# CH32V467RET-R0.net
KiCad netlist of a schematic drawn in Altium Designer
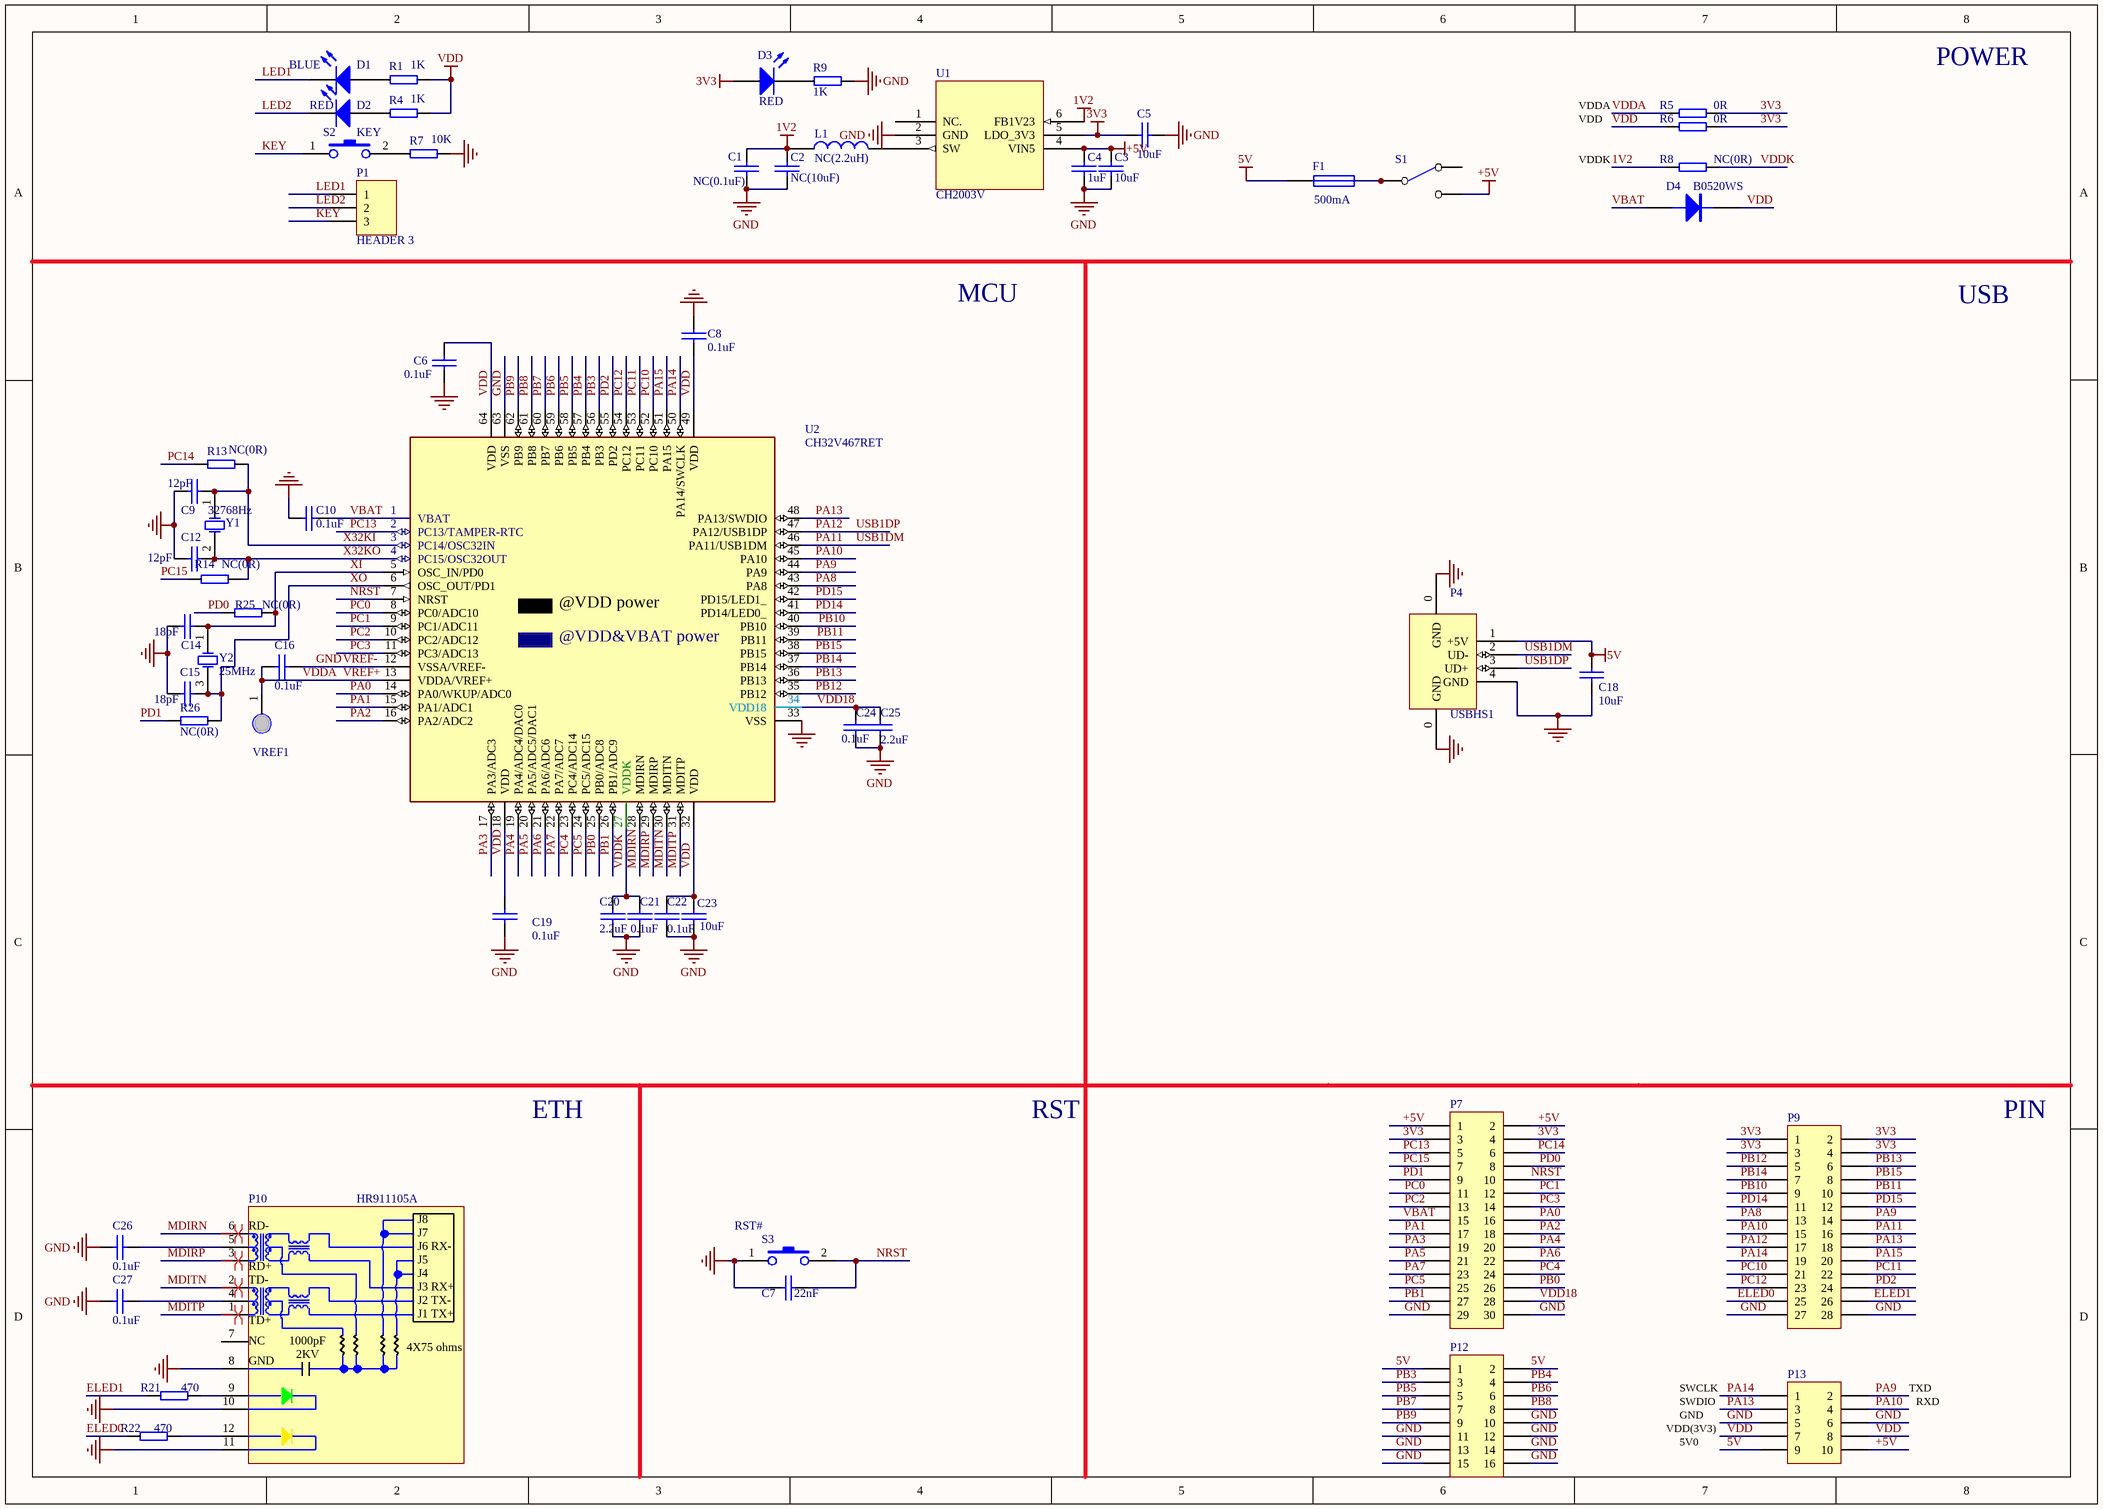
[diagram p0: CH32V467RET-R0.SchDoc]

(export (version "E")
  (design (tool "Eeschema 10.0.6"))
  (components
    (comp (ref "C1")
      (value "NC(0.1uF)")
      (footprint "0402_C")
      (description "Capacitor")
      (libsource (lib "") (part "CAP_2"))
    )
    (comp (ref "C2")
      (value "NC(10uF)")
      (footprint "0603_C")
      (description "Capacitor")
      (libsource (lib "") (part "CAP_1"))
    )
    (comp (ref "C3")
      (value "10uF")
      (footprint "0603_C")
      (description "Capacitor")
      (libsource (lib "") (part "CAP_1"))
    )
    (comp (ref "C4")
      (value "1uF")
      (footprint "0402_C")
      (description "Capacitor")
      (libsource (lib "") (part "CAP_2"))
    )
    (comp (ref "C5")
      (value "10uF")
      (footprint "0603_C")
      (description "Capacitor")
      (libsource (lib "") (part "CAP_1"))
    )
    (comp (ref "C6")
      (value "0.1uF")
      (footprint "0402_C")
      (description "Capacitor")
      (libsource (lib "") (part "CAP_1"))
    )
    (comp (ref "C7")
      (value "22nF")
      (footprint "0402_C")
      (description "Capacitor")
      (libsource (lib "*") (part "CAP"))
    )
    (comp (ref "C8")
      (value "0.1uF")
      (footprint "0402_C")
      (description "Capacitor")
      (libsource (lib "") (part "CAP_1"))
    )
    (comp (ref "C9")
      (value "12pF")
      (footprint "0402_C")
      (description "Capacitor")
      (libsource (lib "") (part "CAP_1"))
    )
    (comp (ref "C10")
      (value "0.1uF")
      (footprint "0402_C")
      (description "Capacitor")
      (libsource (lib "") (part "CAP_1"))
    )
    (comp (ref "C12")
      (value "12pF")
      (footprint "0402_C")
      (description "Capacitor")
      (libsource (lib "") (part "CAP_1"))
    )
    (comp (ref "C14")
      (value "18pF")
      (footprint "0402_C")
      (description "Capacitor")
      (libsource (lib "") (part "CAP_1"))
    )
    (comp (ref "C15")
      (value "18pF")
      (footprint "0402_C")
      (description "Capacitor")
      (libsource (lib "") (part "CAP_1"))
    )
    (comp (ref "C16")
      (value "0.1uF")
      (footprint "0402_C")
      (description "Capacitor")
      (libsource (lib "") (part "CAP_1"))
    )
    (comp (ref "C18")
      (value "10uF")
      (footprint "0603_C")
      (description "Capacitor")
      (libsource (lib "*") (part "CAP"))
    )
    (comp (ref "C19")
      (value "0.1uF")
      (footprint "0402_C")
      (description "Capacitor")
      (libsource (lib "") (part "CAP_1"))
    )
    (comp (ref "C20")
      (value "2.2uF")
      (footprint "0402_C")
      (description "Capacitor")
      (libsource (lib "") (part "CAP_1"))
    )
    (comp (ref "C21")
      (value "0.1uF")
      (footprint "0402_C")
      (description "Capacitor")
      (libsource (lib "") (part "CAP_1"))
    )
    (comp (ref "C22")
      (value "0.1uF")
      (footprint "0402_C")
      (description "Capacitor")
      (libsource (lib "") (part "CAP_1"))
    )
    (comp (ref "C23")
      (value "10uF")
      (footprint "0603_C")
      (description "Capacitor")
      (libsource (lib "wch_sch_others") (part "CAP"))
    )
    (comp (ref "C24")
      (value "0.1uF")
      (footprint "0402_C")
      (description "Capacitor")
      (libsource (lib "") (part "CAP_1"))
    )
    (comp (ref "C25")
      (value "2.2uF")
      (footprint "0402_C")
      (description "Capacitor")
      (libsource (lib "") (part "CAP_1"))
    )
    (comp (ref "C26")
      (value "0.1uF")
      (footprint "0402_C")
      (description "Capacitor")
      (libsource (lib "wch_sch_others") (part "CAP"))
    )
    (comp (ref "C27")
      (value "0.1uF")
      (footprint "0402_C")
      (description "Capacitor")
      (libsource (lib "wch_sch_others") (part "CAP"))
    )
    (comp (ref "D1")
      (value "BLUE")
      (footprint "0603+")
      (description "Typical INFRARED GaAs LED")
      (fields (field (name "PUBLISHER") "Altium Limited"))
      (libsource (lib "*") (part "LED0"))
    )
    (comp (ref "D2")
      (value "RED")
      (footprint "0603+")
      (description "Typical INFRARED GaAs LED")
      (fields (field (name "PUBLISHER") "Altium Limited"))
      (libsource (lib "*") (part "LED0"))
    )
    (comp (ref "D3")
      (value "RED")
      (footprint "0603+")
      (description "Typical INFRARED GaAs LED")
      (fields (field (name "PUBLISHER") "Altium Limited"))
      (libsource (lib "*") (part "LED0"))
    )
    (comp (ref "D4")
      (value "B0520WS")
      (footprint "SOD-323")
      (description "Diode")
      (libsource (lib "*") (part "DIODE"))
    )
    (comp (ref "F1")
      (value "500mA")
      (footprint "0603")
      (description "Fuse")
      (libsource (lib "wch_sch_others") (part "FUSE1"))
    )
    (comp (ref "L1") (value "NC(2.2uH)") (footprint "CD32") (libsource (lib "*") (part "INDUCTOR")))
    (comp (ref "P1")
      (value "HEADER 3")
      (footprint "SIP3-2.54MM")
      (description "Header, 3-Pin")
      (libsource (lib "wch_sch_others") (part "HEADER 3"))
    )
    (comp (ref "P4")
      (value "USBHS1")
      (footprint "USBAF")
      (description "USB Port")
      (libsource (lib "*") (part "USB"))
    )
    (comp (ref "P7")
      (value "HEADER 15x2")
      (footprint "MYPCB:IDC30-2.54MM")
      (description "Header, 15-Pin, Dual row")
      (libsource (lib "wch_sch_others") (part "HEADER 15x2"))
    )
    (comp (ref "P9")
      (value "HEADER 14x2")
      (footprint "MYPCB:IDC28-2.54MM")
      (description "Header, 14-Pin, Dual row")
      (libsource (lib "wch_sch_others") (part "HEADER 14x2"))
    )
    (comp (ref "P10") (value "HR911105A") (footprint "HR911105A") (libsource (lib "*") (part "HR911105A")))
    (comp (ref "P12")
      (value "Ppin")
      (footprint "IDC16-2.54mm")
      (description "Header, 8-Pin, Dual row, Right Angle")
      (fields (field (name "PUBLISHER") "Altium Limited"))
      (libsource (lib "Miscellaneous Connectors") (part "Header 8X2H"))
    )
    (comp (ref "P13")
      (value "LINK")
      (footprint "IDC10-2.54mm")
      (description "Header, 5-Pin, Dual row, Right Angle")
      (fields (field (name "PUBLISHER") "Altium Limited"))
      (libsource (lib "Miscellaneous Connectors") (part "Header 5X2H"))
    )
    (comp (ref "R1") (value "1K") (footprint "0402") (libsource (lib "wch_sch_others") (part "RES")))
    (comp (ref "R4") (value "1K") (footprint "0402") (libsource (lib "wch_sch_others") (part "RES")))
    (comp (ref "R5") (value "0R") (footprint "0402") (libsource (lib "*") (part "R")))
    (comp (ref "R6") (value "0R") (footprint "0402") (libsource (lib "*") (part "R")))
    (comp (ref "R7") (value "10K") (footprint "0402") (libsource (lib "wch_sch_others") (part "RES")))
    (comp (ref "R8") (value "NC(0R)") (footprint "0402") (libsource (lib "*") (part "R")))
    (comp (ref "R9") (value "1K") (footprint "0402") (libsource (lib "wch_sch_others") (part "RES")))
    (comp (ref "R13") (value "NC(0R)") (footprint "0402") (libsource (lib "wch_sch_others") (part "RES")))
    (comp (ref "R14") (value "NC(0R)") (footprint "0402") (libsource (lib "wch_sch_others") (part "RES")))
    (comp (ref "R21") (value "470") (footprint "0402") (libsource (lib "wch_sch_others") (part "RES")))
    (comp (ref "R22") (value "470") (footprint "0402") (libsource (lib "wch_sch_others") (part "RES")))
    (comp (ref "R25") (value "NC(0R)") (footprint "0402") (libsource (lib "wch_sch_others") (part "RES")))
    (comp (ref "R26") (value "NC(0R)") (footprint "0402") (libsource (lib "wch_sch_others") (part "RES")))
    (comp (ref "S1") (value "SW SPDT") (footprint "SW1") (libsource (lib "*") (part "SW SPDT")))
    (comp (ref "S2")
      (value "KEY")
      (footprint "SMD_6.1x3.65x2.5mm-KEY")
      (libsource (lib "wch_sch_others") (part "KEY1"))
    )
    (comp (ref "S3")
      (value "RST#")
      (footprint "SMD_6.1x3.65x2.5mm-KEY")
      (libsource (lib "wch_sch_others") (part "KEY1"))
    )
    (comp (ref "U1")
      (value "CH2003V")
      (footprint "SOT-23-6")
      (description "Step-Down DC-DC Converter, 5V input, 1.23V * 800mA output, with LDO 3.3V * 200mA")
      (libsource (lib "CHXXX") (part "CH2003V"))
    )
    (comp (ref "U2")
      (value "CH32V467RET")
      (footprint "LQFP64_7X7")
      (description "RISC-V FPU HD-MCU, 175MHz, USB_480M, 100M Ethernet & Phy, CAN, ADC, DAC, SRAM")
      (libsource (lib "CHXXX") (part "CH32V467RET"))
    )
    (comp (ref "VREF1")
      (value "PAD")
      (footprint "TESTPOINT1")
      (description "焊盘")
      (libsource (lib "wch_sch_others") (part "PAD"))
    )
    (comp (ref "Y1")
      (value "32768Hz")
      (footprint "FC-135")
      (description "Crystal Oscillator")
      (fields (field (name "PUBLISHER") "Altium Limited"))
      (libsource (lib "*") (part "XTAL"))
    )
    (comp (ref "Y2")
      (value "25MHz")
      (footprint "XT3225")
      (description "Crystal Oscillator")
      (fields (field (name "PUBLISHER") "Altium Limited"))
      (libsource (lib "") (part "XTAL_1"))
    )
  )
  (nets
    (net (code "1") (name "+5V") (class "Default")
      (node (ref "C3") (pin "2") (pinfunction "2_2") (pintype "passive"))
      (node (ref "C4") (pin "2") (pinfunction "2_2") (pintype "passive"))
      (node (ref "P13") (pin "10") (pinfunction "10_10") (pintype "passive"))
      (node (ref "P7") (pin "1") (pinfunction "1_1") (pintype "passive"))
      (node (ref "P7") (pin "2") (pinfunction "2_2") (pintype "passive"))
      (node (ref "S1") (pin "2") (pinfunction "NC_2") (pintype "passive"))
      (node (ref "U1") (pin "4") (pinfunction "VIN5_4") (pintype "power_in"))
    )
    (net (code "3") (name "/ELED0") (class "Default")
      (node (ref "P9") (pin "25") (pinfunction "25_25") (pintype "passive"))
      (node (ref "R22") (pin "1") (pintype "passive"))
    )
    (net (code "4") (name "/ELED1") (class "Default")
      (node (ref "P9") (pin "26") (pinfunction "26_26") (pintype "passive"))
      (node (ref "R21") (pin "1") (pintype "passive"))
    )
    (net (code "5") (name "/KEY") (class "Default")
      (node (ref "P1") (pin "3") (pinfunction "3_3") (pintype "passive"))
      (node (ref "S2") (pin "1") (pinfunction "1_1") (pintype "passive"))
    )
    (net (code "6") (name "/LED1") (class "Default")
      (node (ref "D1") (pin "2") (pinfunction "K_2") (pintype "passive"))
      (node (ref "P1") (pin "1") (pinfunction "1_1") (pintype "passive"))
    )
    (net (code "7") (name "/LED2") (class "Default")
      (node (ref "D2") (pin "2") (pinfunction "K_2") (pintype "passive"))
      (node (ref "P1") (pin "2") (pinfunction "2_2") (pintype "passive"))
    )
    (net (code "8") (name "/MDIRN") (class "Default")
      (node (ref "P10") (pin "6") (pintype "passive"))
      (node (ref "U2") (pin "28") (pinfunction "MDIRN_28") (pintype "bidirectional"))
    )
    (net (code "9") (name "/MDIRP") (class "Default")
      (node (ref "P10") (pin "3") (pintype "passive"))
      (node (ref "U2") (pin "29") (pinfunction "MDIRP_29") (pintype "bidirectional"))
    )
    (net (code "10") (name "/MDITN") (class "Default")
      (node (ref "P10") (pin "2") (pintype "passive"))
      (node (ref "U2") (pin "30") (pinfunction "MDITN_30") (pintype "bidirectional"))
    )
    (net (code "11") (name "/MDITP") (class "Default")
      (node (ref "P10") (pin "1") (pintype "passive"))
      (node (ref "U2") (pin "31") (pinfunction "MDITP_31") (pintype "bidirectional"))
    )
    (net (code "12") (name "/NRST") (class "Default")
      (node (ref "C7") (pin "2") (pinfunction "2_2") (pintype "passive"))
      (node (ref "P7") (pin "10") (pinfunction "10_10") (pintype "passive"))
      (node (ref "S3") (pin "2") (pinfunction "2_2") (pintype "passive"))
      (node (ref "U2") (pin "7") (pinfunction "NRST_7") (pintype "input"))
    )
    (net (code "13") (name "/PA0") (class "Default")
      (node (ref "P7") (pin "16") (pinfunction "16_16") (pintype "passive"))
      (node (ref "U2") (pin "14") (pinfunction "PA0/WKUP/ADC0_14") (pintype "bidirectional"))
    )
    (net (code "14") (name "/PA1") (class "Default")
      (node (ref "P7") (pin "17") (pinfunction "17_17") (pintype "passive"))
      (node (ref "U2") (pin "15") (pinfunction "PA1/ADC1_15") (pintype "bidirectional"))
    )
    (net (code "15") (name "/PA2") (class "Default")
      (node (ref "P7") (pin "18") (pinfunction "18_18") (pintype "passive"))
      (node (ref "U2") (pin "16") (pinfunction "PA2/ADC2_16") (pintype "bidirectional"))
    )
    (net (code "16") (name "/PA3") (class "Default")
      (node (ref "P7") (pin "19") (pinfunction "19_19") (pintype "passive"))
      (node (ref "U2") (pin "17") (pinfunction "PA3/ADC3_17") (pintype "bidirectional"))
    )
    (net (code "17") (name "/PA4") (class "Default")
      (node (ref "P7") (pin "20") (pinfunction "20_20") (pintype "passive"))
      (node (ref "U2") (pin "19") (pinfunction "PA4/ADC4/DAC0_19") (pintype "bidirectional"))
    )
    (net (code "18") (name "/PA5") (class "Default")
      (node (ref "P7") (pin "21") (pinfunction "21_21") (pintype "passive"))
      (node (ref "U2") (pin "20") (pinfunction "PA5/ADC5/DAC1_20") (pintype "bidirectional"))
    )
    (net (code "19") (name "/PA6") (class "Default")
      (node (ref "P7") (pin "22") (pinfunction "22_22") (pintype "passive"))
      (node (ref "U2") (pin "21") (pinfunction "PA6/ADC6_21") (pintype "bidirectional"))
    )
    (net (code "20") (name "/PA7") (class "Default")
      (node (ref "P7") (pin "23") (pinfunction "23_23") (pintype "passive"))
      (node (ref "U2") (pin "22") (pinfunction "PA7/ADC7_22") (pintype "bidirectional"))
    )
    (net (code "21") (name "/PA8") (class "Default")
      (node (ref "P9") (pin "13") (pinfunction "13_13") (pintype "passive"))
      (node (ref "U2") (pin "43") (pinfunction "PA8_43") (pintype "bidirectional"))
    )
    (net (code "22") (name "/PA9") (class "Default")
      (node (ref "P13") (pin "2") (pinfunction "2_2") (pintype "passive"))
      (node (ref "P9") (pin "14") (pinfunction "14_14") (pintype "passive"))
      (node (ref "U2") (pin "44") (pinfunction "PA9_44") (pintype "bidirectional"))
    )
    (net (code "23") (name "/PA10") (class "Default")
      (node (ref "P13") (pin "4") (pinfunction "4_4") (pintype "passive"))
      (node (ref "P9") (pin "15") (pinfunction "15_15") (pintype "passive"))
      (node (ref "U2") (pin "45") (pinfunction "PA10_45") (pintype "bidirectional"))
    )
    (net (code "24") (name "/PA11") (class "Default")
      (node (ref "P4") (pin "2") (pinfunction "UD-_2") (pintype "bidirectional"))
      (node (ref "P9") (pin "16") (pinfunction "16_16") (pintype "passive"))
      (node (ref "U2") (pin "46") (pinfunction "PA11/USB1DM_46") (pintype "bidirectional"))
    )
    (net (code "25") (name "/PA12") (class "Default")
      (node (ref "P4") (pin "3") (pinfunction "UD+_3") (pintype "bidirectional"))
      (node (ref "P9") (pin "17") (pinfunction "17_17") (pintype "passive"))
      (node (ref "U2") (pin "47") (pinfunction "PA12/USB1DP_47") (pintype "bidirectional"))
    )
    (net (code "26") (name "/PA13") (class "Default")
      (node (ref "P13") (pin "3") (pinfunction "3_3") (pintype "passive"))
      (node (ref "P9") (pin "18") (pinfunction "18_18") (pintype "passive"))
      (node (ref "U2") (pin "48") (pinfunction "PA13/SWDIO_48") (pintype "bidirectional"))
    )
    (net (code "27") (name "/PA14") (class "Default")
      (node (ref "P13") (pin "1") (pinfunction "1_1") (pintype "passive"))
      (node (ref "P9") (pin "19") (pinfunction "19_19") (pintype "passive"))
      (node (ref "U2") (pin "50") (pinfunction "PA14/SWCLK_50") (pintype "bidirectional"))
    )
    (net (code "28") (name "/PA15") (class "Default")
      (node (ref "P9") (pin "20") (pinfunction "20_20") (pintype "passive"))
      (node (ref "U2") (pin "51") (pinfunction "PA15_51") (pintype "bidirectional"))
    )
    (net (code "29") (name "/PB0") (class "Default")
      (node (ref "P7") (pin "26") (pinfunction "26_26") (pintype "passive"))
      (node (ref "U2") (pin "25") (pinfunction "PB0/ADC8_25") (pintype "bidirectional"))
    )
    (net (code "30") (name "/PB1") (class "Default")
      (node (ref "P7") (pin "27") (pinfunction "27_27") (pintype "passive"))
      (node (ref "U2") (pin "26") (pinfunction "PB1/ADC9_26") (pintype "bidirectional"))
    )
    (net (code "31") (name "/PB3") (class "Default")
      (node (ref "P12") (pin "3") (pinfunction "3_3") (pintype "passive"))
      (node (ref "U2") (pin "56") (pinfunction "PB3_56") (pintype "bidirectional"))
    )
    (net (code "32") (name "/PB4") (class "Default")
      (node (ref "P12") (pin "4") (pinfunction "4_4") (pintype "passive"))
      (node (ref "U2") (pin "57") (pinfunction "PB4_57") (pintype "bidirectional"))
    )
    (net (code "33") (name "/PB5") (class "Default")
      (node (ref "P12") (pin "5") (pinfunction "5_5") (pintype "passive"))
      (node (ref "U2") (pin "58") (pinfunction "PB5_58") (pintype "bidirectional"))
    )
    (net (code "34") (name "/PB6") (class "Default")
      (node (ref "P12") (pin "6") (pinfunction "6_6") (pintype "passive"))
      (node (ref "U2") (pin "59") (pinfunction "PB6_59") (pintype "bidirectional"))
    )
    (net (code "35") (name "/PB7") (class "Default")
      (node (ref "P12") (pin "7") (pinfunction "7_7") (pintype "passive"))
      (node (ref "U2") (pin "60") (pinfunction "PB7_60") (pintype "bidirectional"))
    )
    (net (code "36") (name "/PB8") (class "Default")
      (node (ref "P12") (pin "8") (pinfunction "8_8") (pintype "passive"))
      (node (ref "U2") (pin "61") (pinfunction "PB8_61") (pintype "bidirectional"))
    )
    (net (code "37") (name "/PB9") (class "Default")
      (node (ref "P12") (pin "9") (pinfunction "9_9") (pintype "passive"))
      (node (ref "U2") (pin "62") (pinfunction "PB9_62") (pintype "bidirectional"))
    )
    (net (code "38") (name "/PB10") (class "Default")
      (node (ref "P9") (pin "9") (pinfunction "9_9") (pintype "passive"))
      (node (ref "U2") (pin "40") (pinfunction "PB10_40") (pintype "bidirectional"))
    )
    (net (code "39") (name "/PB11") (class "Default")
      (node (ref "P9") (pin "10") (pinfunction "10_10") (pintype "passive"))
      (node (ref "U2") (pin "39") (pinfunction "PB11_39") (pintype "bidirectional"))
    )
    (net (code "40") (name "/PB12") (class "Default")
      (node (ref "P9") (pin "5") (pinfunction "5_5") (pintype "passive"))
      (node (ref "U2") (pin "35") (pinfunction "PB12_35") (pintype "bidirectional"))
    )
    (net (code "41") (name "/PB13") (class "Default")
      (node (ref "P9") (pin "6") (pinfunction "6_6") (pintype "passive"))
      (node (ref "U2") (pin "36") (pinfunction "PB13_36") (pintype "bidirectional"))
    )
    (net (code "42") (name "/PB14") (class "Default")
      (node (ref "P9") (pin "7") (pinfunction "7_7") (pintype "passive"))
      (node (ref "U2") (pin "37") (pinfunction "PB14_37") (pintype "bidirectional"))
    )
    (net (code "43") (name "/PB15") (class "Default")
      (node (ref "P9") (pin "8") (pinfunction "8_8") (pintype "passive"))
      (node (ref "U2") (pin "38") (pinfunction "PB15_38") (pintype "bidirectional"))
    )
    (net (code "44") (name "/PC0") (class "Default")
      (node (ref "P7") (pin "11") (pinfunction "11_11") (pintype "passive"))
      (node (ref "U2") (pin "8") (pinfunction "PC0/ADC10_8") (pintype "bidirectional"))
    )
    (net (code "45") (name "/PC1") (class "Default")
      (node (ref "P7") (pin "12") (pinfunction "12_12") (pintype "passive"))
      (node (ref "U2") (pin "9") (pinfunction "PC1/ADC11_9") (pintype "bidirectional"))
    )
    (net (code "46") (name "/PC2") (class "Default")
      (node (ref "P7") (pin "13") (pinfunction "13_13") (pintype "passive"))
      (node (ref "U2") (pin "10") (pinfunction "PC2/ADC12_10") (pintype "bidirectional"))
    )
    (net (code "47") (name "/PC3") (class "Default")
      (node (ref "P7") (pin "14") (pinfunction "14_14") (pintype "passive"))
      (node (ref "U2") (pin "11") (pinfunction "PC3/ADC13_11") (pintype "bidirectional"))
    )
    (net (code "48") (name "/PC4") (class "Default")
      (node (ref "P7") (pin "24") (pinfunction "24_24") (pintype "passive"))
      (node (ref "U2") (pin "23") (pinfunction "PC4/ADC14_23") (pintype "bidirectional"))
    )
    (net (code "49") (name "/PC5") (class "Default")
      (node (ref "P7") (pin "25") (pinfunction "25_25") (pintype "passive"))
      (node (ref "U2") (pin "24") (pinfunction "PC5/ADC15_24") (pintype "bidirectional"))
    )
    (net (code "50") (name "/PC10") (class "Default")
      (node (ref "P9") (pin "21") (pinfunction "21_21") (pintype "passive"))
      (node (ref "U2") (pin "52") (pinfunction "PC10_52") (pintype "bidirectional"))
    )
    (net (code "51") (name "/PC11") (class "Default")
      (node (ref "P9") (pin "22") (pinfunction "22_22") (pintype "passive"))
      (node (ref "U2") (pin "53") (pinfunction "PC11_53") (pintype "bidirectional"))
    )
    (net (code "52") (name "/PC12") (class "Default")
      (node (ref "P9") (pin "23") (pinfunction "23_23") (pintype "passive"))
      (node (ref "U2") (pin "54") (pinfunction "PC12_54") (pintype "bidirectional"))
    )
    (net (code "53") (name "/PC13") (class "Default")
      (node (ref "P7") (pin "5") (pinfunction "5_5") (pintype "passive"))
      (node (ref "U2") (pin "2") (pinfunction "PC13/TAMPER-RTC_2") (pintype "bidirectional"))
    )
    (net (code "54") (name "/PC14") (class "Default")
      (node (ref "P7") (pin "6") (pinfunction "6_6") (pintype "passive"))
      (node (ref "R13") (pin "1") (pintype "passive"))
    )
    (net (code "55") (name "/PC15") (class "Default")
      (node (ref "P7") (pin "7") (pinfunction "7_7") (pintype "passive"))
      (node (ref "R14") (pin "1") (pintype "passive"))
    )
    (net (code "56") (name "/PD0") (class "Default")
      (node (ref "P7") (pin "8") (pinfunction "8_8") (pintype "passive"))
      (node (ref "R25") (pin "1") (pintype "passive"))
    )
    (net (code "57") (name "/PD1") (class "Default")
      (node (ref "P7") (pin "9") (pinfunction "9_9") (pintype "passive"))
      (node (ref "R26") (pin "2") (pintype "passive"))
    )
    (net (code "58") (name "/PD2") (class "Default")
      (node (ref "P9") (pin "24") (pinfunction "24_24") (pintype "passive"))
      (node (ref "U2") (pin "55") (pinfunction "PD2_55") (pintype "bidirectional"))
    )
    (net (code "59") (name "/PD14") (class "Default")
      (node (ref "P9") (pin "11") (pinfunction "11_11") (pintype "passive"))
      (node (ref "U2") (pin "41") (pinfunction "PD14/LED0__41") (pintype "bidirectional"))
    )
    (net (code "60") (name "/PD15") (class "Default")
      (node (ref "P9") (pin "12") (pinfunction "12_12") (pintype "passive"))
      (node (ref "U2") (pin "42") (pinfunction "PD15/LED1__42") (pintype "bidirectional"))
    )
    (net (code "61") (name "/VBAT") (class "Default")
      (node (ref "C10") (pin "2") (pinfunction "2_2") (pintype "passive"))
      (node (ref "D4") (pin "1") (pinfunction "A_1") (pintype "passive"))
      (node (ref "P7") (pin "15") (pinfunction "15_15") (pintype "passive"))
      (node (ref "U2") (pin "1") (pinfunction "VBAT_1") (pintype "power_in"))
    )
    (net (code "62") (name "/VDD18") (class "Default")
      (node (ref "C24") (pin "2") (pinfunction "2_2") (pintype "passive"))
      (node (ref "C25") (pin "2") (pinfunction "2_2") (pintype "passive"))
      (node (ref "P7") (pin "28") (pinfunction "28_28") (pintype "passive"))
      (node (ref "U2") (pin "34") (pinfunction "VDD18_34") (pintype "power_in"))
    )
    (net (code "63") (name "/VDDA") (class "Default")
      (node (ref "C16") (pin "1") (pinfunction "1_1") (pintype "passive"))
      (node (ref "R5") (pin "2") (pinfunction "2_2") (pintype "passive"))
      (node (ref "U2") (pin "13") (pinfunction "VDDA/VREF+_13") (pintype "power_in"))
      (node (ref "VREF1") (pin "1") (pintype "passive"))
    )
    (net (code "64") (name "/VDDK") (class "Default")
      (node (ref "C20") (pin "2") (pinfunction "2_2") (pintype "passive"))
      (node (ref "C21") (pin "2") (pinfunction "2_2") (pintype "passive"))
      (node (ref "R8") (pin "1") (pinfunction "1_1") (pintype "passive"))
      (node (ref "U2") (pin "27") (pinfunction "VDDK_27") (pintype "power_in"))
    )
    (net (code "65") (name "/X32KI") (class "Default")
      (node (ref "C9") (pin "2") (pinfunction "2_2") (pintype "passive"))
      (node (ref "R13") (pin "2") (pintype "passive"))
      (node (ref "U2") (pin "3") (pinfunction "PC14/OSC32IN_3") (pintype "bidirectional"))
      (node (ref "Y1") (pin "1") (pinfunction "OSC1_1") (pintype "passive"))
    )
    (net (code "66") (name "/X32KO") (class "Default")
      (node (ref "C12") (pin "2") (pinfunction "2_2") (pintype "passive"))
      (node (ref "R14") (pin "2") (pintype "passive"))
      (node (ref "U2") (pin "4") (pinfunction "PC15/OSC32OUT_4") (pintype "bidirectional"))
      (node (ref "Y1") (pin "2") (pinfunction "OSC2_2") (pintype "passive"))
    )
    (net (code "67") (name "/XI") (class "Default")
      (node (ref "C14") (pin "2") (pinfunction "2_2") (pintype "passive"))
      (node (ref "R25") (pin "2") (pintype "passive"))
      (node (ref "U2") (pin "5") (pinfunction "OSC_IN/PD0_5") (pintype "input"))
      (node (ref "Y2") (pin "1") (pinfunction "OSC1_1") (pintype "passive"))
    )
    (net (code "68") (name "/XO") (class "Default")
      (node (ref "C15") (pin "2") (pinfunction "2_2") (pintype "passive"))
      (node (ref "R26") (pin "1") (pintype "passive"))
      (node (ref "U2") (pin "6") (pinfunction "OSC_OUT/PD1_6") (pintype "output"))
      (node (ref "Y2") (pin "3") (pinfunction "OSC2_3") (pintype "passive"))
    )
    (net (code "69") (name "1V2") (class "Default")
      (node (ref "C1") (pin "2") (pinfunction "2_2") (pintype "passive"))
      (node (ref "C2") (pin "2") (pinfunction "2_2") (pintype "passive"))
      (node (ref "L1") (pin "2") (pinfunction "2_2") (pintype "passive"))
      (node (ref "R8") (pin "2") (pinfunction "2_2") (pintype "passive"))
      (node (ref "U1") (pin "6") (pinfunction "FB1V23_6") (pintype "input"))
    )
    (net (code "70") (name "3V3") (class "Default")
      (node (ref "C5") (pin "2") (pinfunction "2_2") (pintype "passive"))
      (node (ref "D3") (pin "1") (pinfunction "A_1") (pintype "passive"))
      (node (ref "P7") (pin "3") (pinfunction "3_3") (pintype "passive"))
      (node (ref "P7") (pin "4") (pinfunction "4_4") (pintype "passive"))
      (node (ref "P9") (pin "1") (pinfunction "1_1") (pintype "passive"))
      (node (ref "P9") (pin "2") (pinfunction "2_2") (pintype "passive"))
      (node (ref "P9") (pin "3") (pinfunction "3_3") (pintype "passive"))
      (node (ref "P9") (pin "4") (pinfunction "4_4") (pintype "passive"))
      (node (ref "R5") (pin "1") (pinfunction "1_1") (pintype "passive"))
      (node (ref "R6") (pin "1") (pinfunction "1_1") (pintype "passive"))
      (node (ref "U1") (pin "5") (pinfunction "LDO_3V3_5") (pintype "power_in"))
    )
    (net (code "71") (name "5V") (class "Default")
      (node (ref "C18") (pin "1") (pinfunction "1_1") (pintype "passive"))
      (node (ref "F1") (pin "1") (pinfunction "1_1") (pintype "passive"))
      (node (ref "P12") (pin "1") (pinfunction "1_1") (pintype "passive"))
      (node (ref "P12") (pin "2") (pinfunction "2_2") (pintype "passive"))
      (node (ref "P13") (pin "9") (pinfunction "9_9") (pintype "passive"))
      (node (ref "P4") (pin "1") (pinfunction "+5V_1") (pintype "power_in"))
    )
    (net (code "72") (name "GND") (class "Default")
      (node (ref "C1") (pin "1") (pinfunction "1_1") (pintype "passive"))
      (node (ref "C10") (pin "1") (pinfunction "1_1") (pintype "passive"))
      (node (ref "C12") (pin "1") (pinfunction "1_1") (pintype "passive"))
      (node (ref "C14") (pin "1") (pinfunction "1_1") (pintype "passive"))
      (node (ref "C15") (pin "1") (pinfunction "1_1") (pintype "passive"))
      (node (ref "C16") (pin "2") (pinfunction "2_2") (pintype "passive"))
      (node (ref "C18") (pin "2") (pinfunction "2_2") (pintype "passive"))
      (node (ref "C19") (pin "1") (pinfunction "1_1") (pintype "passive"))
      (node (ref "C2") (pin "1") (pinfunction "1_1") (pintype "passive"))
      (node (ref "C20") (pin "1") (pinfunction "1_1") (pintype "passive"))
      (node (ref "C21") (pin "1") (pinfunction "1_1") (pintype "passive"))
      (node (ref "C22") (pin "1") (pinfunction "1_1") (pintype "passive"))
      (node (ref "C23") (pin "1") (pinfunction "1_1") (pintype "passive"))
      (node (ref "C24") (pin "1") (pinfunction "1_1") (pintype "passive"))
      (node (ref "C25") (pin "1") (pinfunction "1_1") (pintype "passive"))
      (node (ref "C26") (pin "1") (pinfunction "1_1") (pintype "passive"))
      (node (ref "C27") (pin "1") (pinfunction "1_1") (pintype "passive"))
      (node (ref "C3") (pin "1") (pinfunction "1_1") (pintype "passive"))
      (node (ref "C4") (pin "1") (pinfunction "1_1") (pintype "passive"))
      (node (ref "C5") (pin "1") (pinfunction "1_1") (pintype "passive"))
      (node (ref "C6") (pin "1") (pinfunction "1_1") (pintype "passive"))
      (node (ref "C7") (pin "1") (pinfunction "1_1") (pintype "passive"))
      (node (ref "C8") (pin "2") (pinfunction "2_2") (pintype "passive"))
      (node (ref "C9") (pin "1") (pinfunction "1_1") (pintype "passive"))
      (node (ref "P10") (pin "10") (pintype "passive"))
      (node (ref "P10") (pin "11") (pintype "passive"))
      (node (ref "P10") (pin "8") (pintype "passive"))
      (node (ref "P12") (pin "10") (pinfunction "10_10") (pintype "passive"))
      (node (ref "P12") (pin "11") (pinfunction "11_11") (pintype "passive"))
      (node (ref "P12") (pin "12") (pinfunction "12_12") (pintype "passive"))
      (node (ref "P12") (pin "13") (pinfunction "13_13") (pintype "passive"))
      (node (ref "P12") (pin "14") (pinfunction "14_14") (pintype "passive"))
      (node (ref "P12") (pin "15") (pinfunction "15_15") (pintype "passive"))
      (node (ref "P12") (pin "16") (pinfunction "16_16") (pintype "passive"))
      (node (ref "P13") (pin "5") (pinfunction "5_5") (pintype "passive"))
      (node (ref "P13") (pin "6") (pinfunction "6_6") (pintype "passive"))
      (node (ref "P4") (pin "0") (pinfunction "GND_0") (pintype "power_in"))
      (node (ref "P4") (pin "4") (pinfunction "GND_4") (pintype "power_in"))
      (node (ref "P7") (pin "29") (pinfunction "29_29") (pintype "passive"))
      (node (ref "P7") (pin "30") (pinfunction "30_30") (pintype "passive"))
      (node (ref "P9") (pin "27") (pinfunction "27_27") (pintype "passive"))
      (node (ref "P9") (pin "28") (pinfunction "28_28") (pintype "passive"))
      (node (ref "R7") (pin "1") (pintype "passive"))
      (node (ref "R9") (pin "2") (pintype "passive"))
      (node (ref "S3") (pin "1") (pinfunction "1_1") (pintype "passive"))
      (node (ref "U1") (pin "2") (pinfunction "GND_2") (pintype "power_in"))
      (node (ref "U2") (pin "12") (pinfunction "VSSA/VREF-_12") (pintype "power_in"))
      (node (ref "U2") (pin "33") (pinfunction "VSS_33") (pintype "power_in"))
      (node (ref "U2") (pin "63") (pinfunction "VSS_63") (pintype "power_in"))
    )
    (net (code "73") (name "Net-(C26-Pad2)") (class "Default")
      (node (ref "C26") (pin "2") (pinfunction "2_2") (pintype "passive"))
      (node (ref "P10") (pin "5") (pintype "passive"))
    )
    (net (code "74") (name "Net-(C27-Pad2)") (class "Default")
      (node (ref "C27") (pin "2") (pinfunction "2_2") (pintype "passive"))
      (node (ref "P10") (pin "4") (pintype "passive"))
    )
    (net (code "75") (name "Net-(D1-A)") (class "Default")
      (node (ref "D1") (pin "1") (pinfunction "A_1") (pintype "passive"))
      (node (ref "R1") (pin "2") (pintype "passive"))
    )
    (net (code "76") (name "Net-(D2-A)") (class "Default")
      (node (ref "D2") (pin "1") (pinfunction "A_1") (pintype "passive"))
      (node (ref "R4") (pin "2") (pintype "passive"))
    )
    (net (code "77") (name "Net-(D3-K)") (class "Default")
      (node (ref "D3") (pin "2") (pinfunction "K_2") (pintype "passive"))
      (node (ref "R9") (pin "1") (pintype "passive"))
    )
    (net (code "78") (name "Net-(P10-Pad9)") (class "Default")
      (node (ref "P10") (pin "9") (pintype "passive"))
      (node (ref "R21") (pin "2") (pintype "passive"))
    )
    (net (code "79") (name "Net-(P10-Pad12)") (class "Default")
      (node (ref "P10") (pin "12") (pintype "passive"))
      (node (ref "R22") (pin "2") (pintype "passive"))
    )
    (net (code "80") (name "Net-(R7-Pad2)") (class "Default")
      (node (ref "R7") (pin "2") (pintype "passive"))
      (node (ref "S2") (pin "2") (pinfunction "2_2") (pintype "passive"))
    )
    (net (code "81") (name "Net-(S1-COMMON)") (class "Default")
      (node (ref "F1") (pin "2") (pinfunction "2_2") (pintype "passive"))
      (node (ref "S1") (pin "1") (pinfunction "COMMON_1") (pintype "passive"))
    )
    (net (code "82") (name "Net-(U1-SW)") (class "Default")
      (node (ref "L1") (pin "1") (pinfunction "1_1") (pintype "passive"))
      (node (ref "U1") (pin "3") (pinfunction "SW_3") (pintype "output"))
    )
    (net (code "83") (name "VDD") (class "Default")
      (node (ref "C19") (pin "2") (pinfunction "2_2") (pintype "passive"))
      (node (ref "C22") (pin "2") (pinfunction "2_2") (pintype "passive"))
      (node (ref "C23") (pin "2") (pinfunction "2_2") (pintype "passive"))
      (node (ref "C6") (pin "2") (pinfunction "2_2") (pintype "passive"))
      (node (ref "C8") (pin "1") (pinfunction "1_1") (pintype "passive"))
      (node (ref "D4") (pin "2") (pinfunction "K_2") (pintype "passive"))
      (node (ref "P13") (pin "7") (pinfunction "7_7") (pintype "passive"))
      (node (ref "P13") (pin "8") (pinfunction "8_8") (pintype "passive"))
      (node (ref "R1") (pin "1") (pintype "passive"))
      (node (ref "R4") (pin "1") (pintype "passive"))
      (node (ref "R6") (pin "2") (pinfunction "2_2") (pintype "passive"))
      (node (ref "U2") (pin "18") (pinfunction "VDD_18") (pintype "power_in"))
      (node (ref "U2") (pin "32") (pinfunction "VDD_32") (pintype "power_in"))
      (node (ref "U2") (pin "49") (pinfunction "VDD_49") (pintype "power_in"))
      (node (ref "U2") (pin "64") (pinfunction "VDD_64") (pintype "power_in"))
    )
    (net (code "84") (name "unconnected-(P10-Pad7)") (class "Default")
      (node (ref "P10") (pin "7") (pintype "passive"))
    )
    (net (code "85") (name "unconnected-(S1-NO-Pad3)") (class "Default")
      (node (ref "S1") (pin "3") (pinfunction "NO_3") (pintype "passive"))
    )
    (net (code "86") (name "unconnected-(U1-NC.-Pad1)") (class "Default")
      (node (ref "U1") (pin "1") (pinfunction "NC._1") (pintype "passive"))
    )
  )
)
